# 2021-01-21_HALO_Main_Board-Autorouted.net
KiCad netlist of a schematic drawn in EAGLE
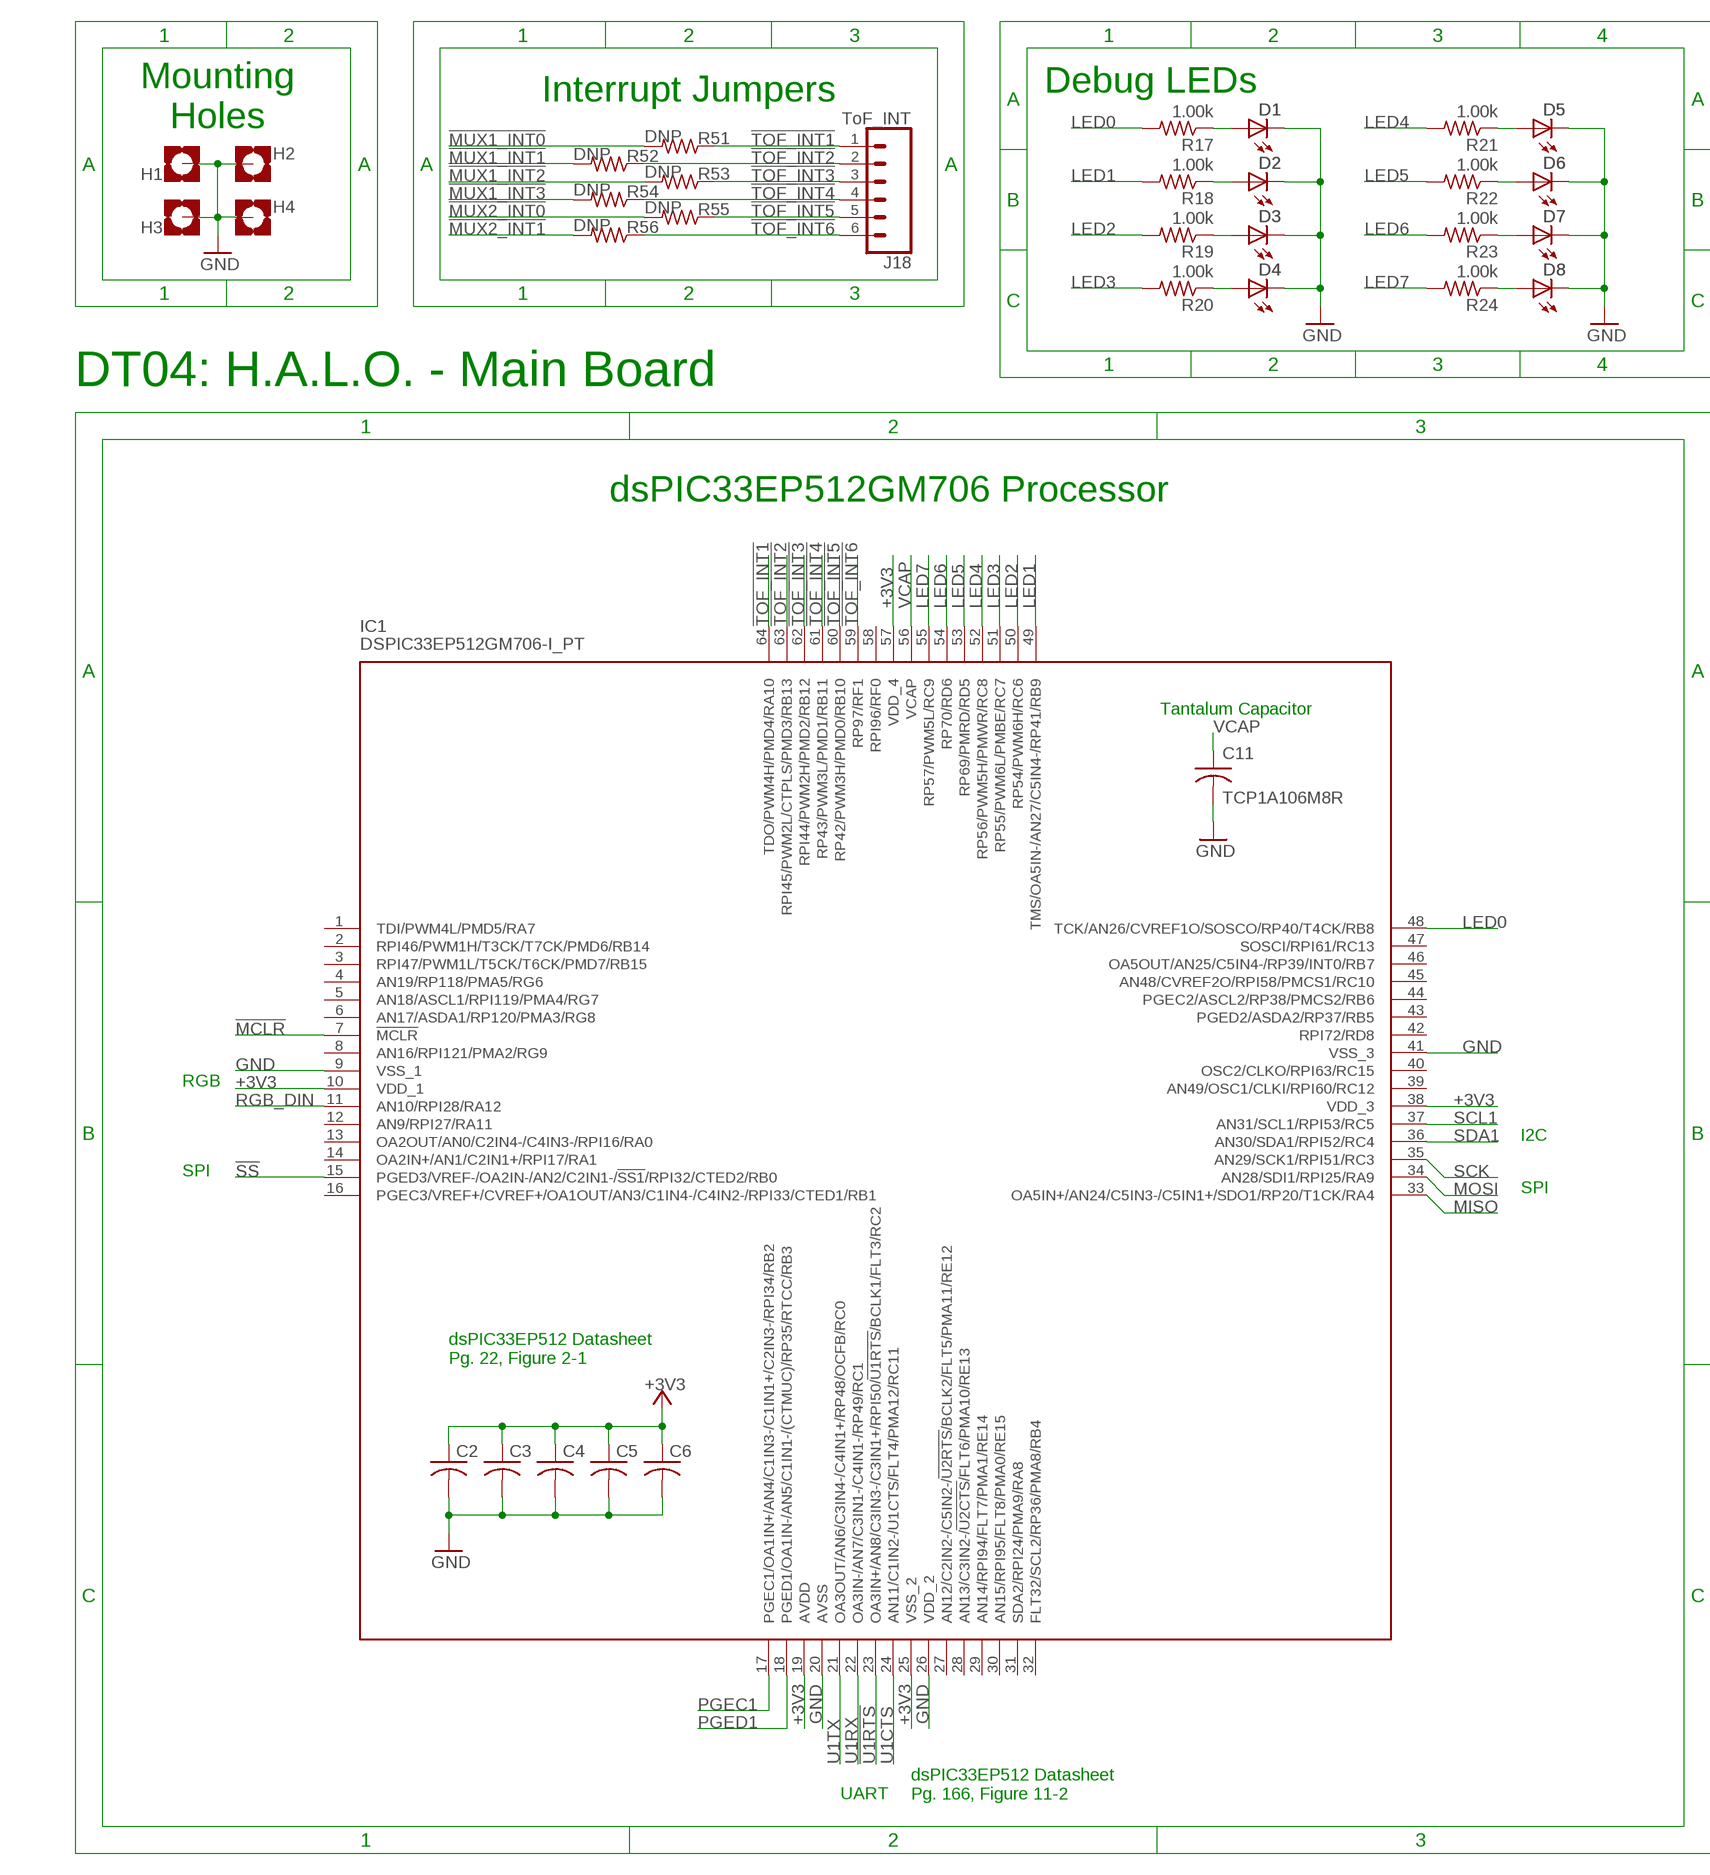
[diagram p0: schematic, sheet 1, part 1 of 2]
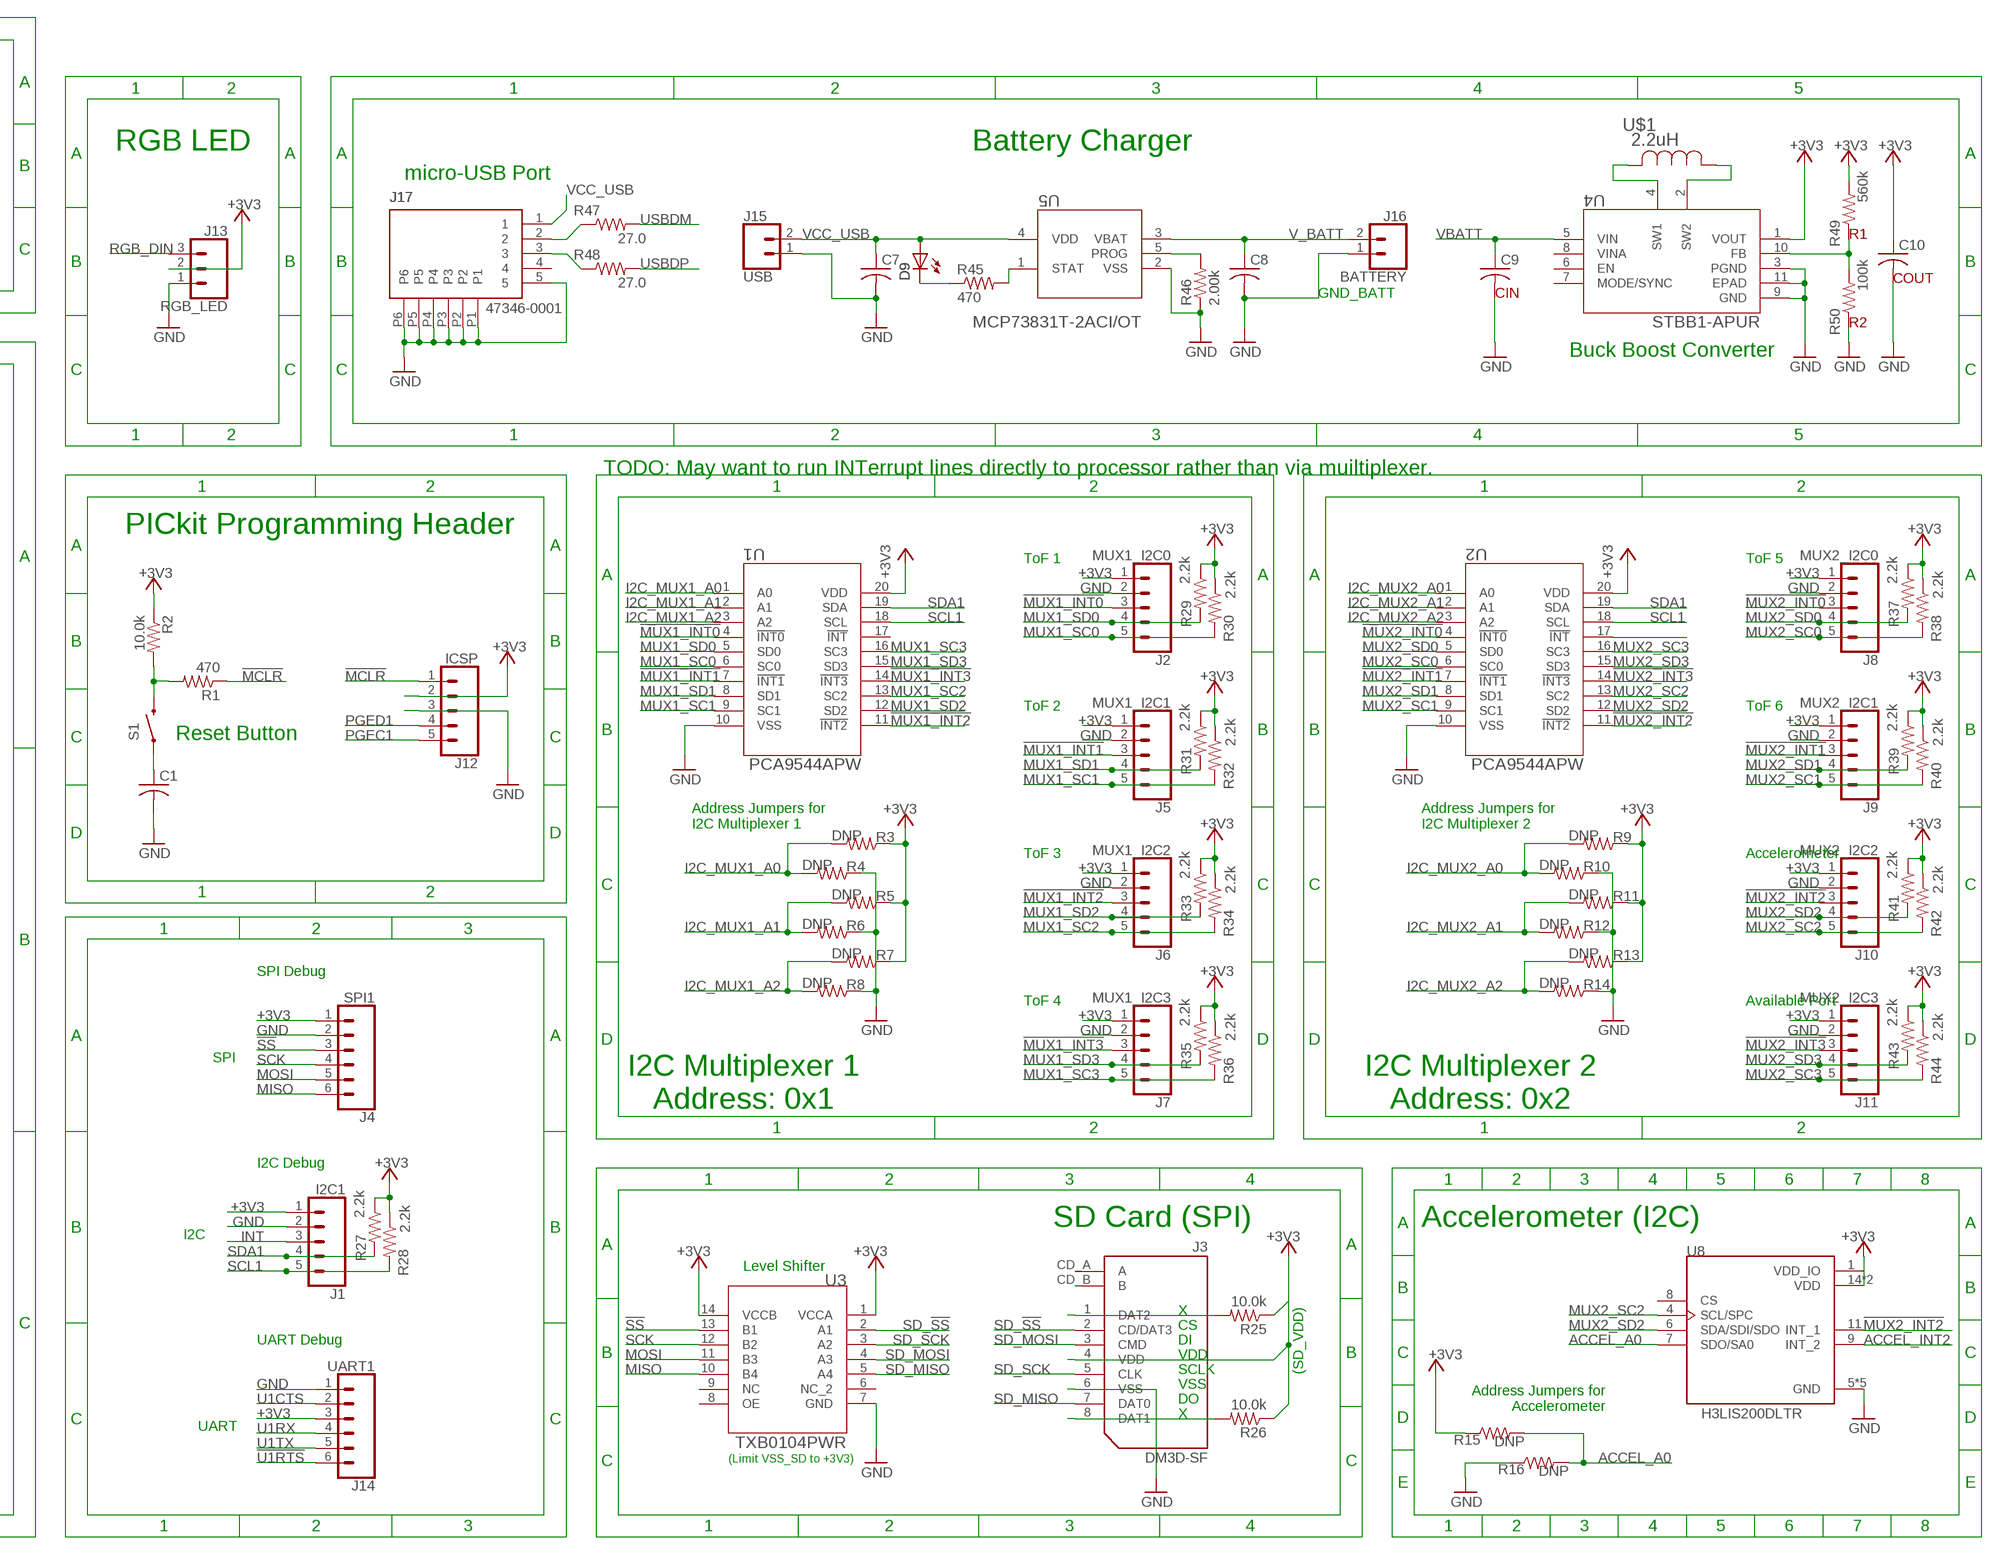
[diagram p1: schematic, sheet 1, part 2 of 2]

(export (version "E")
  (design (tool "Eeschema 10.0.6"))
  (components
    (comp (ref "C1")
      (value "0.1uF")
      (footprint "eagle-import:C0805")
      (libsource (lib "eagle-import") (part "C-USC0805"))
    )
    (comp (ref "C2")
      (value "0.1uF")
      (footprint "eagle-import:C0805")
      (libsource (lib "eagle-import") (part "C-USC0805"))
    )
    (comp (ref "C3")
      (value "0.1uF")
      (footprint "eagle-import:C0805")
      (libsource (lib "eagle-import") (part "C-USC0805"))
    )
    (comp (ref "C4")
      (value "0.1uF")
      (footprint "eagle-import:C0805")
      (libsource (lib "eagle-import") (part "C-USC0805"))
    )
    (comp (ref "C5")
      (value "0.1uF")
      (footprint "eagle-import:C0805")
      (libsource (lib "eagle-import") (part "C-USC0805"))
    )
    (comp (ref "C6")
      (value "0.1uF")
      (footprint "eagle-import:C0805")
      (libsource (lib "eagle-import") (part "C-USC0805"))
    )
    (comp (ref "C7")
      (value "4.7uF")
      (footprint "eagle-import:C0805")
      (libsource (lib "eagle-import") (part "C-USC0805"))
    )
    (comp (ref "C8")
      (value "4.7uF")
      (footprint "eagle-import:C0805")
      (libsource (lib "eagle-import") (part "C-USC0805"))
    )
    (comp (ref "C9")
      (value "10uF")
      (footprint "eagle-import:C0805")
      (libsource (lib "eagle-import") (part "C-USC0805"))
    )
    (comp (ref "C10")
      (value "22uF")
      (footprint "eagle-import:C0805")
      (libsource (lib "eagle-import") (part "C-USC0805"))
    )
    (comp (ref "C11")
      (value "TCP1A106M8R")
      (footprint "eagle-import:TCP_ROM")
      (libsource (lib "eagle-import") (part "TCP1A106M8R"))
    )
    (comp (ref "D1")
      (value "CHIP-LED0805")
      (footprint "eagle-import:CHIP-LED0805")
      (libsource (lib "eagle-import") (part "CHIP-LED0805"))
    )
    (comp (ref "D2")
      (value "CHIP-LED0805")
      (footprint "eagle-import:CHIP-LED0805")
      (libsource (lib "eagle-import") (part "CHIP-LED0805"))
    )
    (comp (ref "D3")
      (value "CHIP-LED0805")
      (footprint "eagle-import:CHIP-LED0805")
      (libsource (lib "eagle-import") (part "CHIP-LED0805"))
    )
    (comp (ref "D4")
      (value "CHIP-LED0805")
      (footprint "eagle-import:CHIP-LED0805")
      (libsource (lib "eagle-import") (part "CHIP-LED0805"))
    )
    (comp (ref "D5")
      (value "CHIP-LED0805")
      (footprint "eagle-import:CHIP-LED0805")
      (libsource (lib "eagle-import") (part "CHIP-LED0805"))
    )
    (comp (ref "D6")
      (value "CHIP-LED0805")
      (footprint "eagle-import:CHIP-LED0805")
      (libsource (lib "eagle-import") (part "CHIP-LED0805"))
    )
    (comp (ref "D7")
      (value "CHIP-LED0805")
      (footprint "eagle-import:CHIP-LED0805")
      (libsource (lib "eagle-import") (part "CHIP-LED0805"))
    )
    (comp (ref "D8")
      (value "CHIP-LED0805")
      (footprint "eagle-import:CHIP-LED0805")
      (libsource (lib "eagle-import") (part "CHIP-LED0805"))
    )
    (comp (ref "D9")
      (value "CHIP-LED0805")
      (footprint "eagle-import:CHIP-LED0805")
      (libsource (lib "eagle-import") (part "CHIP-LED0805"))
    )
    (comp (ref "H1")
      (value "MOUNT-PAD-SQUARE3.0")
      (footprint "eagle-import:3,0-PAD-SQUARE")
      (libsource (lib "eagle-import") (part "MOUNT-PAD-SQUARE3.0"))
    )
    (comp (ref "H2")
      (value "MOUNT-PAD-SQUARE3.0")
      (footprint "eagle-import:3,0-PAD-SQUARE")
      (libsource (lib "eagle-import") (part "MOUNT-PAD-SQUARE3.0"))
    )
    (comp (ref "H3")
      (value "MOUNT-PAD-SQUARE3.0")
      (footprint "eagle-import:3,0-PAD-SQUARE")
      (libsource (lib "eagle-import") (part "MOUNT-PAD-SQUARE3.0"))
    )
    (comp (ref "H4")
      (value "MOUNT-PAD-SQUARE3.0")
      (footprint "eagle-import:3,0-PAD-SQUARE")
      (libsource (lib "eagle-import") (part "MOUNT-PAD-SQUARE3.0"))
    )
    (comp (ref "IC1")
      (value "DSPIC33EP512GM706-I_PT")
      (footprint "eagle-import:QFP50P1200X1200X120-64N")
      (fields
        (field (name "ARROW_PART_NUMBER") "DSPIC33EP512GM706-I/PT")
        (field (name "MOUSER_PART_NUMBER") "579-512GM706-I/PT")
      )
      (libsource (lib "eagle-import") (part "DSPIC33EP512GM706-I_PT"))
    )
    (comp (ref "J1")
      (value "I2C1")
      (footprint "eagle-import:1X05")
      (libsource (lib "eagle-import") (part "CONN_05"))
    )
    (comp (ref "J2")
      (value "MUX1_I2C0")
      (footprint "eagle-import:1X05")
      (libsource (lib "eagle-import") (part "CONN_05"))
    )
    (comp (ref "J3")
      (value "DM3D-SF")
      (footprint "eagle-import:SD_CARD")
      (fields (field (name "PARTNO") "AS-ITM-00047"))
      (libsource (lib "eagle-import") (part "AS-ITM-00047"))
    )
    (comp (ref "J4")
      (value "SPI1")
      (footprint "eagle-import:1X06")
      (libsource (lib "eagle-import") (part "CONN_06SILK_FEMALE_PTH"))
    )
    (comp (ref "J5")
      (value "MUX1_I2C1")
      (footprint "eagle-import:1X05")
      (libsource (lib "eagle-import") (part "CONN_05"))
    )
    (comp (ref "J6")
      (value "MUX1_I2C2")
      (footprint "eagle-import:1X05")
      (libsource (lib "eagle-import") (part "CONN_05"))
    )
    (comp (ref "J7")
      (value "MUX1_I2C3")
      (footprint "eagle-import:1X05")
      (libsource (lib "eagle-import") (part "CONN_05"))
    )
    (comp (ref "J8")
      (value "MUX2_I2C0")
      (footprint "eagle-import:1X05")
      (libsource (lib "eagle-import") (part "CONN_05"))
    )
    (comp (ref "J9")
      (value "MUX2_I2C1")
      (footprint "eagle-import:1X05")
      (libsource (lib "eagle-import") (part "CONN_05"))
    )
    (comp (ref "J10")
      (value "MUX2_I2C2")
      (footprint "eagle-import:1X05")
      (libsource (lib "eagle-import") (part "CONN_05"))
    )
    (comp (ref "J11")
      (value "MUX2_I2C3")
      (footprint "eagle-import:1X05")
      (libsource (lib "eagle-import") (part "CONN_05"))
    )
    (comp (ref "J12")
      (value "ICSP")
      (footprint "eagle-import:1X05")
      (libsource (lib "eagle-import") (part "CONN_05"))
    )
    (comp (ref "J13")
      (value "RGB_LED")
      (footprint "eagle-import:1X03_LOCK")
      (libsource (lib "eagle-import") (part "CONN_03LOCK"))
    )
    (comp (ref "J14")
      (value "UART1")
      (footprint "eagle-import:1X06")
      (libsource (lib "eagle-import") (part "CONN_06SILK_FEMALE_PTH"))
    )
    (comp (ref "J15")
      (value "USB")
      (footprint "eagle-import:1X02")
      (libsource (lib "eagle-import") (part "CONN_02"))
    )
    (comp (ref "J16")
      (value "BATTERY")
      (footprint "eagle-import:1X02")
      (libsource (lib "eagle-import") (part "CONN_02"))
    )
    (comp (ref "J17")
      (value "47346-0001")
      (footprint "eagle-import:MICRO_USB")
      (fields (field (name "PARTNO") "AS-ITM-00021") (field (name "PARTNO_1") "AS-ITM-00021"))
      (libsource (lib "eagle-import") (part "AS-ITM-00021"))
    )
    (comp (ref "J18")
      (value "ToF_INT")
      (footprint "eagle-import:1X06")
      (libsource (lib "eagle-import") (part "CONN_06SILK_FEMALE_PTH"))
    )
    (comp (ref "R1")
      (value "470")
      (footprint "eagle-import:R0805")
      (libsource (lib "eagle-import") (part "R-US_R0805"))
    )
    (comp (ref "R2")
      (value "10.0k")
      (footprint "eagle-import:R0805")
      (libsource (lib "eagle-import") (part "R-US_R0805"))
    )
    (comp (ref "R3")
      (value "DNP")
      (footprint "eagle-import:R0805")
      (libsource (lib "eagle-import") (part "R-US_R0805"))
    )
    (comp (ref "R4")
      (value "DNP")
      (footprint "eagle-import:R0805")
      (libsource (lib "eagle-import") (part "R-US_R0805"))
    )
    (comp (ref "R5")
      (value "DNP")
      (footprint "eagle-import:R0805")
      (libsource (lib "eagle-import") (part "R-US_R0805"))
    )
    (comp (ref "R6")
      (value "DNP")
      (footprint "eagle-import:R0805")
      (libsource (lib "eagle-import") (part "R-US_R0805"))
    )
    (comp (ref "R7")
      (value "DNP")
      (footprint "eagle-import:R0805")
      (libsource (lib "eagle-import") (part "R-US_R0805"))
    )
    (comp (ref "R8")
      (value "DNP")
      (footprint "eagle-import:R0805")
      (libsource (lib "eagle-import") (part "R-US_R0805"))
    )
    (comp (ref "R9")
      (value "DNP")
      (footprint "eagle-import:R0805")
      (libsource (lib "eagle-import") (part "R-US_R0805"))
    )
    (comp (ref "R10")
      (value "DNP")
      (footprint "eagle-import:R0805")
      (libsource (lib "eagle-import") (part "R-US_R0805"))
    )
    (comp (ref "R11")
      (value "DNP")
      (footprint "eagle-import:R0805")
      (libsource (lib "eagle-import") (part "R-US_R0805"))
    )
    (comp (ref "R12")
      (value "DNP")
      (footprint "eagle-import:R0805")
      (libsource (lib "eagle-import") (part "R-US_R0805"))
    )
    (comp (ref "R13")
      (value "DNP")
      (footprint "eagle-import:R0805")
      (libsource (lib "eagle-import") (part "R-US_R0805"))
    )
    (comp (ref "R14")
      (value "DNP")
      (footprint "eagle-import:R0805")
      (libsource (lib "eagle-import") (part "R-US_R0805"))
    )
    (comp (ref "R15")
      (value "DNP")
      (footprint "eagle-import:R0805")
      (libsource (lib "eagle-import") (part "R-US_R0805"))
    )
    (comp (ref "R16")
      (value "DNP")
      (footprint "eagle-import:R0805")
      (libsource (lib "eagle-import") (part "R-US_R0805"))
    )
    (comp (ref "R17")
      (value "1.00k")
      (footprint "eagle-import:R0805")
      (libsource (lib "eagle-import") (part "R-US_R0805"))
    )
    (comp (ref "R18")
      (value "1.00k")
      (footprint "eagle-import:R0805")
      (libsource (lib "eagle-import") (part "R-US_R0805"))
    )
    (comp (ref "R19")
      (value "1.00k")
      (footprint "eagle-import:R0805")
      (libsource (lib "eagle-import") (part "R-US_R0805"))
    )
    (comp (ref "R20")
      (value "1.00k")
      (footprint "eagle-import:R0805")
      (libsource (lib "eagle-import") (part "R-US_R0805"))
    )
    (comp (ref "R21")
      (value "1.00k")
      (footprint "eagle-import:R0805")
      (libsource (lib "eagle-import") (part "R-US_R0805"))
    )
    (comp (ref "R22")
      (value "1.00k")
      (footprint "eagle-import:R0805")
      (libsource (lib "eagle-import") (part "R-US_R0805"))
    )
    (comp (ref "R23")
      (value "1.00k")
      (footprint "eagle-import:R0805")
      (libsource (lib "eagle-import") (part "R-US_R0805"))
    )
    (comp (ref "R24")
      (value "1.00k")
      (footprint "eagle-import:R0805")
      (libsource (lib "eagle-import") (part "R-US_R0805"))
    )
    (comp (ref "R25")
      (value "10.0k")
      (footprint "eagle-import:R0805")
      (libsource (lib "eagle-import") (part "R-US_R0805"))
    )
    (comp (ref "R26")
      (value "10.0k")
      (footprint "eagle-import:R0805")
      (libsource (lib "eagle-import") (part "R-US_R0805"))
    )
    (comp (ref "R27")
      (value "2.2k")
      (footprint "eagle-import:R0805")
      (libsource (lib "eagle-import") (part "R-US_R0805"))
    )
    (comp (ref "R28")
      (value "2.2k")
      (footprint "eagle-import:R0805")
      (libsource (lib "eagle-import") (part "R-US_R0805"))
    )
    (comp (ref "R29")
      (value "2.2k")
      (footprint "eagle-import:R0805")
      (libsource (lib "eagle-import") (part "R-US_R0805"))
    )
    (comp (ref "R30")
      (value "2.2k")
      (footprint "eagle-import:R0805")
      (libsource (lib "eagle-import") (part "R-US_R0805"))
    )
    (comp (ref "R31")
      (value "2.2k")
      (footprint "eagle-import:R0805")
      (libsource (lib "eagle-import") (part "R-US_R0805"))
    )
    (comp (ref "R32")
      (value "2.2k")
      (footprint "eagle-import:R0805")
      (libsource (lib "eagle-import") (part "R-US_R0805"))
    )
    (comp (ref "R33")
      (value "2.2k")
      (footprint "eagle-import:R0805")
      (libsource (lib "eagle-import") (part "R-US_R0805"))
    )
    (comp (ref "R34")
      (value "2.2k")
      (footprint "eagle-import:R0805")
      (libsource (lib "eagle-import") (part "R-US_R0805"))
    )
    (comp (ref "R35")
      (value "2.2k")
      (footprint "eagle-import:R0805")
      (libsource (lib "eagle-import") (part "R-US_R0805"))
    )
    (comp (ref "R36")
      (value "2.2k")
      (footprint "eagle-import:R0805")
      (libsource (lib "eagle-import") (part "R-US_R0805"))
    )
    (comp (ref "R37")
      (value "2.2k")
      (footprint "eagle-import:R0805")
      (libsource (lib "eagle-import") (part "R-US_R0805"))
    )
    (comp (ref "R38")
      (value "2.2k")
      (footprint "eagle-import:R0805")
      (libsource (lib "eagle-import") (part "R-US_R0805"))
    )
    (comp (ref "R39")
      (value "2.2k")
      (footprint "eagle-import:R0805")
      (libsource (lib "eagle-import") (part "R-US_R0805"))
    )
    (comp (ref "R40")
      (value "2.2k")
      (footprint "eagle-import:R0805")
      (libsource (lib "eagle-import") (part "R-US_R0805"))
    )
    (comp (ref "R41")
      (value "2.2k")
      (footprint "eagle-import:R0805")
      (libsource (lib "eagle-import") (part "R-US_R0805"))
    )
    (comp (ref "R42")
      (value "2.2k")
      (footprint "eagle-import:R0805")
      (libsource (lib "eagle-import") (part "R-US_R0805"))
    )
    (comp (ref "R43")
      (value "2.2k")
      (footprint "eagle-import:R0805")
      (libsource (lib "eagle-import") (part "R-US_R0805"))
    )
    (comp (ref "R44")
      (value "2.2k")
      (footprint "eagle-import:R0805")
      (libsource (lib "eagle-import") (part "R-US_R0805"))
    )
    (comp (ref "R45")
      (value "470")
      (footprint "eagle-import:R0805")
      (libsource (lib "eagle-import") (part "R-US_R0805"))
    )
    (comp (ref "R46")
      (value "2.00k")
      (footprint "eagle-import:R0805")
      (libsource (lib "eagle-import") (part "R-US_R0805"))
    )
    (comp (ref "R47")
      (value "27.0")
      (footprint "eagle-import:R0805")
      (libsource (lib "eagle-import") (part "R-US_R0805"))
    )
    (comp (ref "R48")
      (value "27.0")
      (footprint "eagle-import:R0805")
      (libsource (lib "eagle-import") (part "R-US_R0805"))
    )
    (comp (ref "R49")
      (value "560k")
      (footprint "eagle-import:R0805")
      (libsource (lib "eagle-import") (part "R-US_R0805"))
    )
    (comp (ref "R50")
      (value "100k")
      (footprint "eagle-import:R0805")
      (libsource (lib "eagle-import") (part "R-US_R0805"))
    )
    (comp (ref "R51")
      (value "DNP")
      (footprint "eagle-import:R0805")
      (libsource (lib "eagle-import") (part "R-US_R0805"))
    )
    (comp (ref "R52")
      (value "DNP")
      (footprint "eagle-import:R0805")
      (libsource (lib "eagle-import") (part "R-US_R0805"))
    )
    (comp (ref "R53")
      (value "DNP")
      (footprint "eagle-import:R0805")
      (libsource (lib "eagle-import") (part "R-US_R0805"))
    )
    (comp (ref "R54")
      (value "DNP")
      (footprint "eagle-import:R0805")
      (libsource (lib "eagle-import") (part "R-US_R0805"))
    )
    (comp (ref "R55")
      (value "DNP")
      (footprint "eagle-import:R0805")
      (libsource (lib "eagle-import") (part "R-US_R0805"))
    )
    (comp (ref "R56")
      (value "DNP")
      (footprint "eagle-import:R0805")
      (libsource (lib "eagle-import") (part "R-US_R0805"))
    )
    (comp (ref "S1")
      (value "SWITCH-MOMENTARY-2SMD-4")
      (footprint "eagle-import:TACTILE_SWITCH_TALL")
      (libsource (lib "eagle-import") (part "SWITCH-MOMENTARY-2SMD-4"))
    )
    (comp (ref "U$1")
      (value "2.2uH")
      (footprint "eagle-import:IND_4028_TDK")
      (libsource (lib "eagle-import") (part "IND"))
    )
    (comp (ref "U1")
      (value "PCA9544APW")
      (footprint "eagle-import:SOT360-1_NXP")
      (libsource (lib "eagle-import") (part "PCA9544APW"))
    )
    (comp (ref "U2")
      (value "PCA9544APW")
      (footprint "eagle-import:SOT360-1_NXP")
      (libsource (lib "eagle-import") (part "PCA9544APW"))
    )
    (comp (ref "U3")
      (value "TXB0104PWR")
      (footprint "eagle-import:PW14")
      (fields
        (field (name "GENERIC_PART_NUMBER") "TXB0104")
        (field (name "MANUFACTURER") "Texas Instruments")
      )
      (libsource (lib "eagle-import") (part "TXB0104PWR"))
    )
    (comp (ref "U4")
      (value "STBB1-APUR")
      (footprint "eagle-import:SON_B1-APUR_STM")
      (libsource (lib "eagle-import") (part "STBB1-APUR"))
    )
    (comp (ref "U5")
      (value "MCP73831T-2ACI/OT")
      (footprint "eagle-import:SOT-23-5_MC_MCH")
      (libsource (lib "eagle-import") (part "MCP73831T-2ACI/OT"))
    )
    (comp (ref "U8")
      (value "H3LIS200DLTR")
      (footprint "eagle-import:PQFN50P300X300X100-16N")
      (fields (field (name "DIGI-KEY_PART_NUMBER") "497-15698-1-ND") (field (name "MF") "STMicroelectronics"))
      (libsource (lib "eagle-import") (part "H3LIS200DLTR"))
    )
  )
  (nets
    (net (code "1") (name "+3V3") (class "Default")
      (node (ref "C10") (pin "1") (pinfunction "1_1") (pintype "passive"))
      (node (ref "C2") (pin "1") (pinfunction "1_1") (pintype "passive"))
      (node (ref "C3") (pin "1") (pinfunction "1_1") (pintype "passive"))
      (node (ref "C4") (pin "1") (pinfunction "1_1") (pintype "passive"))
      (node (ref "C5") (pin "1") (pinfunction "1_1") (pintype "passive"))
      (node (ref "C6") (pin "1") (pinfunction "1_1") (pintype "passive"))
      (node (ref "IC1") (pin "10") (pinfunction "VDD_1_10") (pintype "bidirectional"))
      (node (ref "IC1") (pin "19") (pinfunction "AVDD_19") (pintype "bidirectional"))
      (node (ref "IC1") (pin "25") (pinfunction "VSS_2_25") (pintype "bidirectional"))
      (node (ref "IC1") (pin "38") (pinfunction "VDD_3_38") (pintype "bidirectional"))
      (node (ref "IC1") (pin "57") (pinfunction "VDD_4_57") (pintype "bidirectional"))
      (node (ref "J1") (pin "1") (pinfunction "1_1") (pintype "passive"))
      (node (ref "J10") (pin "1") (pinfunction "1_1") (pintype "passive"))
      (node (ref "J11") (pin "1") (pinfunction "1_1") (pintype "passive"))
      (node (ref "J12") (pin "2") (pinfunction "2_2") (pintype "passive"))
      (node (ref "J13") (pin "2") (pinfunction "2_2") (pintype "passive"))
      (node (ref "J14") (pin "3") (pinfunction "3_3") (pintype "passive"))
      (node (ref "J2") (pin "1") (pinfunction "1_1") (pintype "passive"))
      (node (ref "J3") (pin "4") (pinfunction "VDD_4") (pintype "bidirectional"))
      (node (ref "J4") (pin "1") (pinfunction "1_1") (pintype "passive"))
      (node (ref "J5") (pin "1") (pinfunction "1_1") (pintype "passive"))
      (node (ref "J6") (pin "1") (pinfunction "1_1") (pintype "passive"))
      (node (ref "J7") (pin "1") (pinfunction "1_1") (pintype "passive"))
      (node (ref "J8") (pin "1") (pinfunction "1_1") (pintype "passive"))
      (node (ref "J9") (pin "1") (pinfunction "1_1") (pintype "passive"))
      (node (ref "R11") (pin "1") (pinfunction "1_1") (pintype "passive"))
      (node (ref "R13") (pin "1") (pinfunction "1_1") (pintype "passive"))
      (node (ref "R15") (pin "1") (pinfunction "1_1") (pintype "passive"))
      (node (ref "R2") (pin "1") (pinfunction "1_1") (pintype "passive"))
      (node (ref "R25") (pin "1") (pinfunction "1_1") (pintype "passive"))
      (node (ref "R26") (pin "1") (pinfunction "1_1") (pintype "passive"))
      (node (ref "R27") (pin "1") (pinfunction "1_1") (pintype "passive"))
      (node (ref "R28") (pin "1") (pinfunction "1_1") (pintype "passive"))
      (node (ref "R29") (pin "1") (pinfunction "1_1") (pintype "passive"))
      (node (ref "R3") (pin "1") (pinfunction "1_1") (pintype "passive"))
      (node (ref "R30") (pin "1") (pinfunction "1_1") (pintype "passive"))
      (node (ref "R31") (pin "1") (pinfunction "1_1") (pintype "passive"))
      (node (ref "R32") (pin "1") (pinfunction "1_1") (pintype "passive"))
      (node (ref "R33") (pin "1") (pinfunction "1_1") (pintype "passive"))
      (node (ref "R34") (pin "1") (pinfunction "1_1") (pintype "passive"))
      (node (ref "R35") (pin "1") (pinfunction "1_1") (pintype "passive"))
      (node (ref "R36") (pin "1") (pinfunction "1_1") (pintype "passive"))
      (node (ref "R37") (pin "1") (pinfunction "1_1") (pintype "passive"))
      (node (ref "R38") (pin "1") (pinfunction "1_1") (pintype "passive"))
      (node (ref "R39") (pin "1") (pinfunction "1_1") (pintype "passive"))
      (node (ref "R40") (pin "1") (pinfunction "1_1") (pintype "passive"))
      (node (ref "R41") (pin "1") (pinfunction "1_1") (pintype "passive"))
      (node (ref "R42") (pin "1") (pinfunction "1_1") (pintype "passive"))
      (node (ref "R43") (pin "1") (pinfunction "1_1") (pintype "passive"))
      (node (ref "R44") (pin "1") (pinfunction "1_1") (pintype "passive"))
      (node (ref "R49") (pin "2") (pinfunction "2_2") (pintype "passive"))
      (node (ref "R5") (pin "1") (pinfunction "1_1") (pintype "passive"))
      (node (ref "R7") (pin "1") (pinfunction "1_1") (pintype "passive"))
      (node (ref "R9") (pin "1") (pinfunction "1_1") (pintype "passive"))
      (node (ref "U1") (pin "20") (pinfunction "VDD_20") (pintype "passive"))
      (node (ref "U2") (pin "20") (pinfunction "VDD_20") (pintype "passive"))
      (node (ref "U3") (pin "1") (pinfunction "VCCA_1") (pintype "power_in"))
      (node (ref "U3") (pin "14") (pinfunction "VCCB_14") (pintype "power_in"))
      (node (ref "U4") (pin "1") (pinfunction "VOUT_1") (pintype "power_in"))
      (node (ref "U8") (pin "1") (pinfunction "VDD_IO_1") (pintype "power_in"))
      (node (ref "U8") (pin "14") (pinfunction "VDD_14") (pintype "power_in"))
      (node (ref "U8") (pin "15") (pinfunction "VDD_15") (pintype "power_in"))
    )
    (net (code "2") (name "/ACCEL_A0") (class "Default")
      (node (ref "R15") (pin "2") (pinfunction "2_2") (pintype "passive"))
      (node (ref "R16") (pin "2") (pinfunction "2_2") (pintype "passive"))
      (node (ref "U8") (pin "7") (pinfunction "SDO/SA0_7") (pintype "output"))
    )
    (net (code "3") (name "/ACCEL_INT2") (class "Default")
      (node (ref "U8") (pin "9") (pinfunction "INT_2_9") (pintype "output"))
    )
    (net (code "4") (name "/I2C_MUX1_A0") (class "Default")
      (node (ref "R3") (pin "2") (pinfunction "2_2") (pintype "passive"))
      (node (ref "R4") (pin "2") (pinfunction "2_2") (pintype "passive"))
      (node (ref "U1") (pin "1") (pinfunction "A0_1") (pintype "passive"))
    )
    (net (code "5") (name "/I2C_MUX1_A1") (class "Default")
      (node (ref "R5") (pin "2") (pinfunction "2_2") (pintype "passive"))
      (node (ref "R6") (pin "2") (pinfunction "2_2") (pintype "passive"))
      (node (ref "U1") (pin "2") (pinfunction "A1_2") (pintype "passive"))
    )
    (net (code "6") (name "/I2C_MUX1_A2") (class "Default")
      (node (ref "R7") (pin "2") (pinfunction "2_2") (pintype "passive"))
      (node (ref "R8") (pin "2") (pinfunction "2_2") (pintype "passive"))
      (node (ref "U1") (pin "3") (pinfunction "A2_3") (pintype "passive"))
    )
    (net (code "7") (name "/I2C_MUX2_A0") (class "Default")
      (node (ref "R10") (pin "2") (pinfunction "2_2") (pintype "passive"))
      (node (ref "R9") (pin "2") (pinfunction "2_2") (pintype "passive"))
      (node (ref "U2") (pin "1") (pinfunction "A0_1") (pintype "passive"))
    )
    (net (code "8") (name "/I2C_MUX2_A1") (class "Default")
      (node (ref "R11") (pin "2") (pinfunction "2_2") (pintype "passive"))
      (node (ref "R12") (pin "2") (pinfunction "2_2") (pintype "passive"))
      (node (ref "U2") (pin "2") (pinfunction "A1_2") (pintype "passive"))
    )
    (net (code "9") (name "/I2C_MUX2_A2") (class "Default")
      (node (ref "R13") (pin "2") (pinfunction "2_2") (pintype "passive"))
      (node (ref "R14") (pin "2") (pinfunction "2_2") (pintype "passive"))
      (node (ref "U2") (pin "3") (pinfunction "A2_3") (pintype "passive"))
    )
    (net (code "10") (name "/INT") (class "Default")
      (node (ref "J1") (pin "3") (pinfunction "3_3") (pintype "passive"))
    )
    (net (code "11") (name "/LED0") (class "Default")
      (node (ref "IC1") (pin "48") (pinfunction "TCK/AN26/CVREF1O/SOSCO/RP40/T4CK/RB8_48") (pintype "bidirectional"))
      (node (ref "R17") (pin "2") (pinfunction "2_2") (pintype "passive"))
    )
    (net (code "12") (name "/LED1") (class "Default")
      (node (ref "IC1") (pin "49") (pinfunction "TMS/OA5IN-/AN27/C5IN4-/RP41/RB9_49") (pintype "bidirectional"))
      (node (ref "R18") (pin "2") (pinfunction "2_2") (pintype "passive"))
    )
    (net (code "13") (name "/LED2") (class "Default")
      (node (ref "IC1") (pin "50") (pinfunction "RP54/PWM6H/RC6_50") (pintype "bidirectional"))
      (node (ref "R19") (pin "2") (pinfunction "2_2") (pintype "passive"))
    )
    (net (code "14") (name "/LED3") (class "Default")
      (node (ref "IC1") (pin "51") (pinfunction "RP55/PWM6L/PMBE/RC7_51") (pintype "bidirectional"))
      (node (ref "R20") (pin "2") (pinfunction "2_2") (pintype "passive"))
    )
    (net (code "15") (name "/LED4") (class "Default")
      (node (ref "IC1") (pin "52") (pinfunction "RP56/PWM5H/PMWR/RC8_52") (pintype "bidirectional"))
      (node (ref "R21") (pin "2") (pinfunction "2_2") (pintype "passive"))
    )
    (net (code "16") (name "/LED5") (class "Default")
      (node (ref "IC1") (pin "53") (pinfunction "RP69/PMRD/RD5_53") (pintype "bidirectional"))
      (node (ref "R22") (pin "2") (pinfunction "2_2") (pintype "passive"))
    )
    (net (code "17") (name "/LED6") (class "Default")
      (node (ref "IC1") (pin "54") (pinfunction "RP70/RD6_54") (pintype "bidirectional"))
      (node (ref "R23") (pin "2") (pinfunction "2_2") (pintype "passive"))
    )
    (net (code "18") (name "/LED7") (class "Default")
      (node (ref "IC1") (pin "55") (pinfunction "RP57/PWM5L/RC9_55") (pintype "bidirectional"))
      (node (ref "R24") (pin "2") (pinfunction "2_2") (pintype "passive"))
    )
    (net (code "19") (name "/MISO") (class "Default")
      (node (ref "IC1") (pin "33") (pinfunction "OA5IN+/AN24/C5IN3-/C5IN1+/SDO1/RP20/T1CK/RA4_33") (pintype "bidirectional"))
      (node (ref "J4") (pin "6") (pinfunction "6_6") (pintype "passive"))
      (node (ref "U3") (pin "10") (pinfunction "B4_10") (pintype "bidirectional"))
    )
    (net (code "20") (name "/MOSI") (class "Default")
      (node (ref "IC1") (pin "34") (pinfunction "AN28/SDI1/RPI25/RA9_34") (pintype "bidirectional"))
      (node (ref "J4") (pin "5") (pinfunction "5_5") (pintype "passive"))
      (node (ref "U3") (pin "11") (pinfunction "B3_11") (pintype "bidirectional"))
    )
    (net (code "21") (name "/MUX1_SC0") (class "Default")
      (node (ref "J2") (pin "5") (pinfunction "5_5") (pintype "passive"))
      (node (ref "R30") (pin "2") (pinfunction "2_2") (pintype "passive"))
      (node (ref "U1") (pin "6") (pinfunction "SC0_6") (pintype "passive"))
    )
    (net (code "22") (name "/MUX1_SC1") (class "Default")
      (node (ref "J5") (pin "5") (pinfunction "5_5") (pintype "passive"))
      (node (ref "R32") (pin "2") (pinfunction "2_2") (pintype "passive"))
      (node (ref "U1") (pin "9") (pinfunction "SC1_9") (pintype "passive"))
    )
    (net (code "23") (name "/MUX1_SC2") (class "Default")
      (node (ref "J6") (pin "5") (pinfunction "5_5") (pintype "passive"))
      (node (ref "R34") (pin "2") (pinfunction "2_2") (pintype "passive"))
      (node (ref "U1") (pin "13") (pinfunction "SC2_13") (pintype "passive"))
    )
    (net (code "24") (name "/MUX1_SC3") (class "Default")
      (node (ref "J7") (pin "5") (pinfunction "5_5") (pintype "passive"))
      (node (ref "R36") (pin "2") (pinfunction "2_2") (pintype "passive"))
      (node (ref "U1") (pin "16") (pinfunction "SC3_16") (pintype "passive"))
    )
    (net (code "25") (name "/MUX1_SD0") (class "Default")
      (node (ref "J2") (pin "4") (pinfunction "4_4") (pintype "passive"))
      (node (ref "R29") (pin "2") (pinfunction "2_2") (pintype "passive"))
      (node (ref "U1") (pin "5") (pinfunction "SD0_5") (pintype "passive"))
    )
    (net (code "26") (name "/MUX1_SD1") (class "Default")
      (node (ref "J5") (pin "4") (pinfunction "4_4") (pintype "passive"))
      (node (ref "R31") (pin "2") (pinfunction "2_2") (pintype "passive"))
      (node (ref "U1") (pin "8") (pinfunction "SD1_8") (pintype "passive"))
    )
    (net (code "27") (name "/MUX1_SD2") (class "Default")
      (node (ref "J6") (pin "4") (pinfunction "4_4") (pintype "passive"))
      (node (ref "R33") (pin "2") (pinfunction "2_2") (pintype "passive"))
      (node (ref "U1") (pin "12") (pinfunction "SD2_12") (pintype "passive"))
    )
    (net (code "28") (name "/MUX1_SD3") (class "Default")
      (node (ref "J7") (pin "4") (pinfunction "4_4") (pintype "passive"))
      (node (ref "R35") (pin "2") (pinfunction "2_2") (pintype "passive"))
      (node (ref "U1") (pin "15") (pinfunction "SD3_15") (pintype "passive"))
    )
    (net (code "29") (name "/MUX2_SC0") (class "Default")
      (node (ref "J8") (pin "5") (pinfunction "5_5") (pintype "passive"))
      (node (ref "R38") (pin "2") (pinfunction "2_2") (pintype "passive"))
      (node (ref "U2") (pin "6") (pinfunction "SC0_6") (pintype "passive"))
    )
    (net (code "30") (name "/MUX2_SC1") (class "Default")
      (node (ref "J9") (pin "5") (pinfunction "5_5") (pintype "passive"))
      (node (ref "R40") (pin "2") (pinfunction "2_2") (pintype "passive"))
      (node (ref "U2") (pin "9") (pinfunction "SC1_9") (pintype "passive"))
    )
    (net (code "31") (name "/MUX2_SC2") (class "Default")
      (node (ref "J10") (pin "5") (pinfunction "5_5") (pintype "passive"))
      (node (ref "R42") (pin "2") (pinfunction "2_2") (pintype "passive"))
      (node (ref "U2") (pin "13") (pinfunction "SC2_13") (pintype "passive"))
      (node (ref "U8") (pin "4") (pinfunction "SCL/SPC_4") (pintype "input"))
    )
    (net (code "32") (name "/MUX2_SC3") (class "Default")
      (node (ref "J11") (pin "5") (pinfunction "5_5") (pintype "passive"))
      (node (ref "R44") (pin "2") (pinfunction "2_2") (pintype "passive"))
      (node (ref "U2") (pin "16") (pinfunction "SC3_16") (pintype "passive"))
    )
    (net (code "33") (name "/MUX2_SD0") (class "Default")
      (node (ref "J8") (pin "4") (pinfunction "4_4") (pintype "passive"))
      (node (ref "R37") (pin "2") (pinfunction "2_2") (pintype "passive"))
      (node (ref "U2") (pin "5") (pinfunction "SD0_5") (pintype "passive"))
    )
    (net (code "34") (name "/MUX2_SD1") (class "Default")
      (node (ref "J9") (pin "4") (pinfunction "4_4") (pintype "passive"))
      (node (ref "R39") (pin "2") (pinfunction "2_2") (pintype "passive"))
      (node (ref "U2") (pin "8") (pinfunction "SD1_8") (pintype "passive"))
    )
    (net (code "35") (name "/MUX2_SD2") (class "Default")
      (node (ref "J10") (pin "4") (pinfunction "4_4") (pintype "passive"))
      (node (ref "R41") (pin "2") (pinfunction "2_2") (pintype "passive"))
      (node (ref "U2") (pin "12") (pinfunction "SD2_12") (pintype "passive"))
      (node (ref "U8") (pin "6") (pinfunction "SDA/SDI/SDO_6") (pintype "bidirectional"))
    )
    (net (code "36") (name "/MUX2_SD3") (class "Default")
      (node (ref "J11") (pin "4") (pinfunction "4_4") (pintype "passive"))
      (node (ref "R43") (pin "2") (pinfunction "2_2") (pintype "passive"))
      (node (ref "U2") (pin "15") (pinfunction "SD3_15") (pintype "passive"))
    )
    (net (code "37") (name "/PGEC1") (class "Default")
      (node (ref "IC1") (pin "17") (pinfunction "PGEC1/OA1IN+/AN4/C1IN3-/C1IN1+/C2IN3-/RPI34/RB2_17") (pintype "bidirectional"))
      (node (ref "J12") (pin "5") (pinfunction "5_5") (pintype "passive"))
    )
    (net (code "38") (name "/PGED1") (class "Default")
      (node (ref "IC1") (pin "18") (pinfunction "PGED1/OA1IN-/AN5/C1IN1-/(CTMUC)/RP35/RTCC/RB3_18") (pintype "bidirectional"))
      (node (ref "J12") (pin "4") (pinfunction "4_4") (pintype "passive"))
    )
    (net (code "39") (name "/RGB_DIN") (class "Default")
      (node (ref "IC1") (pin "11") (pinfunction "AN10/RPI28/RA12_11") (pintype "bidirectional"))
      (node (ref "J13") (pin "3") (pinfunction "3_3") (pintype "passive"))
    )
    (net (code "40") (name "/SCK") (class "Default")
      (node (ref "IC1") (pin "35") (pinfunction "AN29/SCK1/RPI51/RC3_35") (pintype "bidirectional"))
      (node (ref "J4") (pin "4") (pinfunction "4_4") (pintype "passive"))
      (node (ref "U3") (pin "12") (pinfunction "B2_12") (pintype "bidirectional"))
    )
    (net (code "41") (name "/SCL1") (class "Default")
      (node (ref "IC1") (pin "37") (pinfunction "AN31/SCL1/RPI53/RC5_37") (pintype "bidirectional"))
      (node (ref "J1") (pin "5") (pinfunction "5_5") (pintype "passive"))
      (node (ref "R28") (pin "2") (pinfunction "2_2") (pintype "passive"))
      (node (ref "U1") (pin "18") (pinfunction "SCL_18") (pintype "passive"))
      (node (ref "U2") (pin "18") (pinfunction "SCL_18") (pintype "passive"))
    )
    (net (code "42") (name "/SDA1") (class "Default")
      (node (ref "IC1") (pin "36") (pinfunction "AN30/SDA1/RPI52/RC4_36") (pintype "bidirectional"))
      (node (ref "J1") (pin "4") (pinfunction "4_4") (pintype "passive"))
      (node (ref "R27") (pin "2") (pinfunction "2_2") (pintype "passive"))
      (node (ref "U1") (pin "19") (pinfunction "SDA_19") (pintype "passive"))
      (node (ref "U2") (pin "19") (pinfunction "SDA_19") (pintype "passive"))
    )
    (net (code "43") (name "/SD_MISO") (class "Default")
      (node (ref "J3") (pin "7") (pinfunction "DAT0_7") (pintype "bidirectional"))
      (node (ref "U3") (pin "5") (pinfunction "A4_5") (pintype "bidirectional"))
    )
    (net (code "44") (name "/SD_MOSI") (class "Default")
      (node (ref "J3") (pin "3") (pinfunction "CMD_3") (pintype "bidirectional"))
      (node (ref "U3") (pin "4") (pinfunction "A3_4") (pintype "bidirectional"))
    )
    (net (code "45") (name "/SD_SCK") (class "Default")
      (node (ref "J3") (pin "5") (pinfunction "CLK_5") (pintype "bidirectional"))
      (node (ref "U3") (pin "3") (pinfunction "A2_3") (pintype "bidirectional"))
    )
    (net (code "46") (name "/SD_~{SS}") (class "Default")
      (node (ref "J3") (pin "2") (pinfunction "CD/DAT3_2") (pintype "bidirectional"))
      (node (ref "U3") (pin "2") (pinfunction "A1_2") (pintype "bidirectional"))
    )
    (net (code "47") (name "/U1CTS") (class "Default")
      (node (ref "IC1") (pin "24") (pinfunction "AN11/C1IN2-/U1CTS/FLT4/PMA12/RC11_24") (pintype "bidirectional"))
      (node (ref "J14") (pin "2") (pinfunction "2_2") (pintype "passive"))
    )
    (net (code "48") (name "/U1RX") (class "Default")
      (node (ref "IC1") (pin "22") (pinfunction "OA3IN-/AN7/C3IN1-/C4IN1-/RP49/RC1_22") (pintype "bidirectional"))
      (node (ref "J14") (pin "4") (pinfunction "4_4") (pintype "passive"))
    )
    (net (code "49") (name "/U1TX") (class "Default")
      (node (ref "IC1") (pin "21") (pinfunction "OA3OUT/AN6/C3IN4-/C4IN1+/RP48/OCFB/RC0_21") (pintype "bidirectional"))
      (node (ref "J14") (pin "5") (pinfunction "5_5") (pintype "passive"))
    )
    (net (code "50") (name "/USBDM") (class "Default")
      (node (ref "R47") (pin "2") (pinfunction "2_2") (pintype "passive"))
    )
    (net (code "51") (name "/USBDP") (class "Default")
      (node (ref "R48") (pin "2") (pinfunction "2_2") (pintype "passive"))
    )
    (net (code "52") (name "/VBATT") (class "Default")
      (node (ref "C9") (pin "1") (pinfunction "1_1") (pintype "passive"))
      (node (ref "U4") (pin "5") (pinfunction "VIN_5") (pintype "power_in"))
    )
    (net (code "53") (name "/VCAP") (class "Default")
      (node (ref "C11") (pin "1") (pinfunction "1_1") (pintype "passive"))
      (node (ref "IC1") (pin "56") (pinfunction "VCAP_56") (pintype "bidirectional"))
    )
    (net (code "54") (name "/VCC_USB") (class "Default")
      (node (ref "C7") (pin "1") (pinfunction "1_1") (pintype "passive"))
      (node (ref "D9") (pin "A") (pinfunction "A_A") (pintype "passive"))
      (node (ref "J15") (pin "2") (pinfunction "2_2") (pintype "passive"))
      (node (ref "J17") (pin "1") (pinfunction "1_1") (pintype "bidirectional"))
      (node (ref "U5") (pin "4") (pinfunction "VDD_4") (pintype "passive"))
    )
    (net (code "55") (name "/VINA") (class "Default")
      (node (ref "U4") (pin "8") (pinfunction "VINA_8") (pintype "power_in"))
    )
    (net (code "56") (name "/V_BATT") (class "Default")
      (node (ref "C8") (pin "1") (pinfunction "1_1") (pintype "passive"))
      (node (ref "J16") (pin "2") (pinfunction "2_2") (pintype "passive"))
      (node (ref "U5") (pin "3") (pinfunction "VBAT_3") (pintype "passive"))
    )
    (net (code "57") (name "/~{MCLR}") (class "Default")
      (node (ref "IC1") (pin "7") (pinfunction "~{MCLR}_7") (pintype "bidirectional"))
      (node (ref "J12") (pin "1") (pinfunction "1_1") (pintype "passive"))
      (node (ref "R1") (pin "1") (pinfunction "1_1") (pintype "passive"))
    )
    (net (code "58") (name "/~{MUX1_INT0}") (class "Default")
      (node (ref "J2") (pin "3") (pinfunction "3_3") (pintype "passive"))
      (node (ref "R51") (pin "2") (pinfunction "2_2") (pintype "passive"))
      (node (ref "U1") (pin "4") (pinfunction "~{INT0}_4") (pintype "passive"))
    )
    (net (code "59") (name "/~{MUX1_INT1}") (class "Default")
      (node (ref "J5") (pin "3") (pinfunction "3_3") (pintype "passive"))
      (node (ref "R52") (pin "2") (pinfunction "2_2") (pintype "passive"))
      (node (ref "U1") (pin "7") (pinfunction "~{INT1}_7") (pintype "passive"))
    )
    (net (code "60") (name "/~{MUX1_INT2}") (class "Default")
      (node (ref "J6") (pin "3") (pinfunction "3_3") (pintype "passive"))
      (node (ref "R53") (pin "2") (pinfunction "2_2") (pintype "passive"))
      (node (ref "U1") (pin "11") (pinfunction "~{INT2}_11") (pintype "passive"))
    )
    (net (code "61") (name "/~{MUX1_INT3}") (class "Default")
      (node (ref "J7") (pin "3") (pinfunction "3_3") (pintype "passive"))
      (node (ref "R54") (pin "2") (pinfunction "2_2") (pintype "passive"))
      (node (ref "U1") (pin "14") (pinfunction "~{INT3}_14") (pintype "passive"))
    )
    (net (code "62") (name "/~{MUX2_INT0}") (class "Default")
      (node (ref "J8") (pin "3") (pinfunction "3_3") (pintype "passive"))
      (node (ref "R55") (pin "2") (pinfunction "2_2") (pintype "passive"))
      (node (ref "U2") (pin "4") (pinfunction "~{INT0}_4") (pintype "passive"))
    )
    (net (code "63") (name "/~{MUX2_INT1}") (class "Default")
      (node (ref "J9") (pin "3") (pinfunction "3_3") (pintype "passive"))
      (node (ref "R56") (pin "2") (pinfunction "2_2") (pintype "passive"))
      (node (ref "U2") (pin "7") (pinfunction "~{INT1}_7") (pintype "passive"))
    )
    (net (code "64") (name "/~{MUX2_INT2}") (class "Default")
      (node (ref "J10") (pin "3") (pinfunction "3_3") (pintype "passive"))
      (node (ref "U2") (pin "11") (pinfunction "~{INT2}_11") (pintype "passive"))
      (node (ref "U8") (pin "11") (pinfunction "INT_1_11") (pintype "output"))
    )
    (net (code "65") (name "/~{MUX2_INT3}") (class "Default")
      (node (ref "J11") (pin "3") (pinfunction "3_3") (pintype "passive"))
      (node (ref "U2") (pin "14") (pinfunction "~{INT3}_14") (pintype "passive"))
    )
    (net (code "66") (name "/~{SS}") (class "Default")
      (node (ref "IC1") (pin "15") (pinfunction "PGED3/VREF-/OA2IN-/AN2/C2IN1-/~{SS1}/RPI32/CTED2/RB0_15") (pintype "bidirectional"))
      (node (ref "J4") (pin "3") (pinfunction "3_3") (pintype "passive"))
      (node (ref "U3") (pin "13") (pinfunction "B1_13") (pintype "bidirectional"))
    )
    (net (code "67") (name "/~{TOF_INT1}") (class "Default")
      (node (ref "IC1") (pin "64") (pinfunction "TDO/PWM4H/PMD4/RA10_64") (pintype "bidirectional"))
      (node (ref "J18") (pin "1") (pinfunction "1_1") (pintype "passive"))
      (node (ref "R51") (pin "1") (pinfunction "1_1") (pintype "passive"))
    )
    (net (code "68") (name "/~{TOF_INT2}") (class "Default")
      (node (ref "IC1") (pin "63") (pinfunction "RPI45/PWM2L/CTPLS/PMD3/RB13_63") (pintype "bidirectional"))
      (node (ref "J18") (pin "2") (pinfunction "2_2") (pintype "passive"))
      (node (ref "R52") (pin "1") (pinfunction "1_1") (pintype "passive"))
    )
    (net (code "69") (name "/~{TOF_INT3}") (class "Default")
      (node (ref "IC1") (pin "62") (pinfunction "RPI44/PWM2H/PMD2/RB12_62") (pintype "bidirectional"))
      (node (ref "J18") (pin "3") (pinfunction "3_3") (pintype "passive"))
      (node (ref "R53") (pin "1") (pinfunction "1_1") (pintype "passive"))
    )
    (net (code "70") (name "/~{TOF_INT4}") (class "Default")
      (node (ref "IC1") (pin "61") (pinfunction "RP43/PWM3L/PMD1/RB11_61") (pintype "bidirectional"))
      (node (ref "J18") (pin "4") (pinfunction "4_4") (pintype "passive"))
      (node (ref "R54") (pin "1") (pinfunction "1_1") (pintype "passive"))
    )
    (net (code "71") (name "/~{TOF_INT5}") (class "Default")
      (node (ref "IC1") (pin "60") (pinfunction "RP42/PWM3H/PMD0/RB10_60") (pintype "bidirectional"))
      (node (ref "J18") (pin "5") (pinfunction "5_5") (pintype "passive"))
      (node (ref "R55") (pin "1") (pinfunction "1_1") (pintype "passive"))
    )
    (net (code "72") (name "/~{TOF_INT6}") (class "Default")
      (node (ref "IC1") (pin "59") (pinfunction "RP97/RF1_59") (pintype "bidirectional"))
      (node (ref "J18") (pin "6") (pinfunction "6_6") (pintype "passive"))
      (node (ref "R56") (pin "1") (pinfunction "1_1") (pintype "passive"))
    )
    (net (code "73") (name "/~{U1RTS}") (class "Default")
      (node (ref "IC1") (pin "23") (pinfunction "OA3IN+/AN8/C3IN3-/C3IN1+/RPI50/~{U1RTS}/BCLK1/FLT3/RC2_23") (pintype "bidirectional"))
      (node (ref "J14") (pin "6") (pinfunction "6_6") (pintype "passive"))
    )
    (net (code "74") (name "GND") (class "Default")
      (node (ref "C1") (pin "2") (pinfunction "2_2") (pintype "passive"))
      (node (ref "C10") (pin "2") (pinfunction "2_2") (pintype "passive"))
      (node (ref "C11") (pin "2") (pinfunction "2_2") (pintype "passive"))
      (node (ref "C2") (pin "2") (pinfunction "2_2") (pintype "passive"))
      (node (ref "C3") (pin "2") (pinfunction "2_2") (pintype "passive"))
      (node (ref "C4") (pin "2") (pinfunction "2_2") (pintype "passive"))
      (node (ref "C5") (pin "2") (pinfunction "2_2") (pintype "passive"))
      (node (ref "C6") (pin "2") (pinfunction "2_2") (pintype "passive"))
      (node (ref "C7") (pin "2") (pinfunction "2_2") (pintype "passive"))
      (node (ref "C8") (pin "2") (pinfunction "2_2") (pintype "passive"))
      (node (ref "C9") (pin "2") (pinfunction "2_2") (pintype "passive"))
      (node (ref "D1") (pin "C") (pinfunction "C_C") (pintype "passive"))
      (node (ref "D2") (pin "C") (pinfunction "C_C") (pintype "passive"))
      (node (ref "D3") (pin "C") (pinfunction "C_C") (pintype "passive"))
      (node (ref "D4") (pin "C") (pinfunction "C_C") (pintype "passive"))
      (node (ref "D5") (pin "C") (pinfunction "C_C") (pintype "passive"))
      (node (ref "D6") (pin "C") (pinfunction "C_C") (pintype "passive"))
      (node (ref "D7") (pin "C") (pinfunction "C_C") (pintype "passive"))
      (node (ref "D8") (pin "C") (pinfunction "C_C") (pintype "passive"))
      (node (ref "H1") (pin "B3,0") (pinfunction "MOUNT_B3,0") (pintype "passive"))
      (node (ref "H2") (pin "B3,0") (pinfunction "MOUNT_B3,0") (pintype "passive"))
      (node (ref "H3") (pin "B3,0") (pinfunction "MOUNT_B3,0") (pintype "passive"))
      (node (ref "H4") (pin "B3,0") (pinfunction "MOUNT_B3,0") (pintype "passive"))
      (node (ref "IC1") (pin "20") (pinfunction "AVSS_20") (pintype "bidirectional"))
      (node (ref "IC1") (pin "26") (pinfunction "VDD_2_26") (pintype "bidirectional"))
      (node (ref "IC1") (pin "41") (pinfunction "VSS_3_41") (pintype "bidirectional"))
      (node (ref "IC1") (pin "9") (pinfunction "VSS_1_9") (pintype "bidirectional"))
      (node (ref "J1") (pin "2") (pinfunction "2_2") (pintype "passive"))
      (node (ref "J10") (pin "2") (pinfunction "2_2") (pintype "passive"))
      (node (ref "J11") (pin "2") (pinfunction "2_2") (pintype "passive"))
      (node (ref "J12") (pin "3") (pinfunction "3_3") (pintype "passive"))
      (node (ref "J13") (pin "1") (pinfunction "1_1") (pintype "passive"))
      (node (ref "J14") (pin "1") (pinfunction "1_1") (pintype "passive"))
      (node (ref "J15") (pin "1") (pinfunction "1_1") (pintype "passive"))
      (node (ref "J16") (pin "1") (pinfunction "1_1") (pintype "passive"))
      (node (ref "J17") (pin "5") (pinfunction "5_5") (pintype "bidirectional"))
      (node (ref "J17") (pin "P1") (pinfunction "P1_P1") (pintype "bidirectional"))
      (node (ref "J17") (pin "P2") (pinfunction "P2_P2") (pintype "bidirectional"))
      (node (ref "J17") (pin "P3") (pinfunction "P3_P3") (pintype "bidirectional"))
      (node (ref "J17") (pin "P4") (pinfunction "P4_P4") (pintype "bidirectional"))
      (node (ref "J17") (pin "P5") (pinfunction "P5_P5") (pintype "bidirectional"))
      (node (ref "J17") (pin "P6") (pinfunction "P6_P6") (pintype "bidirectional"))
      (node (ref "J2") (pin "2") (pinfunction "2_2") (pintype "passive"))
      (node (ref "J3") (pin "6") (pinfunction "VSS_6") (pintype "bidirectional"))
      (node (ref "J4") (pin "2") (pinfunction "2_2") (pintype "passive"))
      (node (ref "J5") (pin "2") (pinfunction "2_2") (pintype "passive"))
      (node (ref "J6") (pin "2") (pinfunction "2_2") (pintype "passive"))
      (node (ref "J7") (pin "2") (pinfunction "2_2") (pintype "passive"))
      (node (ref "J8") (pin "2") (pinfunction "2_2") (pintype "passive"))
      (node (ref "J9") (pin "2") (pinfunction "2_2") (pintype "passive"))
      (node (ref "R10") (pin "1") (pinfunction "1_1") (pintype "passive"))
      (node (ref "R12") (pin "1") (pinfunction "1_1") (pintype "passive"))
      (node (ref "R14") (pin "1") (pinfunction "1_1") (pintype "passive"))
      (node (ref "R16") (pin "1") (pinfunction "1_1") (pintype "passive"))
      (node (ref "R4") (pin "1") (pinfunction "1_1") (pintype "passive"))
      (node (ref "R46") (pin "1") (pinfunction "1_1") (pintype "passive"))
      (node (ref "R50") (pin "1") (pinfunction "1_1") (pintype "passive"))
      (node (ref "R6") (pin "1") (pinfunction "1_1") (pintype "passive"))
      (node (ref "R8") (pin "1") (pinfunction "1_1") (pintype "passive"))
      (node (ref "U1") (pin "10") (pinfunction "VSS_10") (pintype "passive"))
      (node (ref "U2") (pin "10") (pinfunction "VSS_10") (pintype "passive"))
      (node (ref "U3") (pin "7") (pinfunction "GND_7") (pintype "power_in"))
      (node (ref "U4") (pin "11") (pinfunction "EPAD_11") (pintype "passive"))
      (node (ref "U4") (pin "3") (pinfunction "PGND_3") (pintype "passive"))
      (node (ref "U4") (pin "9") (pinfunction "GND_9") (pintype "passive"))
      (node (ref "U5") (pin "2") (pinfunction "VSS_2") (pintype "passive"))
      (node (ref "U8") (pin "10") (pinfunction "GND_10") (pintype "power_in"))
      (node (ref "U8") (pin "12") (pinfunction "GND_12") (pintype "power_in"))
      (node (ref "U8") (pin "13") (pinfunction "GND_13") (pintype "power_in"))
      (node (ref "U8") (pin "16") (pinfunction "GND_16") (pintype "power_in"))
      (node (ref "U8") (pin "5") (pinfunction "GND_5") (pintype "power_in"))
    )
    (net (code "75") (name "Net-(D1-PadA)") (class "Default")
      (node (ref "D1") (pin "A") (pinfunction "A_A") (pintype "passive"))
      (node (ref "R17") (pin "1") (pinfunction "1_1") (pintype "passive"))
    )
    (net (code "76") (name "Net-(D2-PadA)") (class "Default")
      (node (ref "D2") (pin "A") (pinfunction "A_A") (pintype "passive"))
      (node (ref "R18") (pin "1") (pinfunction "1_1") (pintype "passive"))
    )
    (net (code "77") (name "Net-(D3-PadA)") (class "Default")
      (node (ref "D3") (pin "A") (pinfunction "A_A") (pintype "passive"))
      (node (ref "R19") (pin "1") (pinfunction "1_1") (pintype "passive"))
    )
    (net (code "78") (name "Net-(D4-PadA)") (class "Default")
      (node (ref "D4") (pin "A") (pinfunction "A_A") (pintype "passive"))
      (node (ref "R20") (pin "1") (pinfunction "1_1") (pintype "passive"))
    )
    (net (code "79") (name "Net-(D5-PadA)") (class "Default")
      (node (ref "D5") (pin "A") (pinfunction "A_A") (pintype "passive"))
      (node (ref "R21") (pin "1") (pinfunction "1_1") (pintype "passive"))
    )
    (net (code "80") (name "Net-(D6-PadA)") (class "Default")
      (node (ref "D6") (pin "A") (pinfunction "A_A") (pintype "passive"))
      (node (ref "R22") (pin "1") (pinfunction "1_1") (pintype "passive"))
    )
    (net (code "81") (name "Net-(D7-PadA)") (class "Default")
      (node (ref "D7") (pin "A") (pinfunction "A_A") (pintype "passive"))
      (node (ref "R23") (pin "1") (pinfunction "1_1") (pintype "passive"))
    )
    (net (code "82") (name "Net-(D8-PadA)") (class "Default")
      (node (ref "D8") (pin "A") (pinfunction "A_A") (pintype "passive"))
      (node (ref "R24") (pin "1") (pinfunction "1_1") (pintype "passive"))
    )
    (net (code "83") (name "Net-(D9-PadC)") (class "Default")
      (node (ref "D9") (pin "C") (pinfunction "C_C") (pintype "passive"))
      (node (ref "R45") (pin "1") (pinfunction "1_1") (pintype "passive"))
    )
    (net (code "84") (name "Net-(J3-DAT1)") (class "Default")
      (node (ref "J3") (pin "8") (pinfunction "DAT1_8") (pintype "bidirectional"))
      (node (ref "R26") (pin "2") (pinfunction "2_2") (pintype "passive"))
    )
    (net (code "85") (name "Net-(J3-DAT2)") (class "Default")
      (node (ref "J3") (pin "1") (pinfunction "DAT2_1") (pintype "bidirectional"))
      (node (ref "R25") (pin "2") (pinfunction "2_2") (pintype "passive"))
    )
    (net (code "86") (name "Net-(J17-Pad2)") (class "Default")
      (node (ref "J17") (pin "2") (pinfunction "2_2") (pintype "bidirectional"))
      (node (ref "R47") (pin "1") (pinfunction "1_1") (pintype "passive"))
    )
    (net (code "87") (name "Net-(J17-Pad3)") (class "Default")
      (node (ref "J17") (pin "3") (pinfunction "3_3") (pintype "bidirectional"))
      (node (ref "R48") (pin "1") (pinfunction "1_1") (pintype "passive"))
    )
    (net (code "88") (name "Net-(S1-1)") (class "Default")
      (node (ref "C1") (pin "1") (pinfunction "1_1") (pintype "passive"))
      (node (ref "S1") (pin "A2") (pinfunction "1_A2") (pintype "passive"))
    )
    (net (code "89") (name "Net-(S1-2)") (class "Default")
      (node (ref "R1") (pin "2") (pinfunction "2_2") (pintype "passive"))
      (node (ref "R2") (pin "2") (pinfunction "2_2") (pintype "passive"))
      (node (ref "S1") (pin "B2") (pinfunction "2_B2") (pintype "passive"))
    )
    (net (code "90") (name "Net-(U4-FB)") (class "Default")
      (node (ref "R49") (pin "1") (pinfunction "1_1") (pintype "passive"))
      (node (ref "R50") (pin "2") (pinfunction "2_2") (pintype "passive"))
      (node (ref "U4") (pin "10") (pinfunction "FB_10") (pintype "passive"))
    )
    (net (code "91") (name "Net-(U4-SW1)") (class "Default")
      (node (ref "U$1") (pin "2") (pinfunction "2_2") (pintype "passive"))
      (node (ref "U4") (pin "4") (pinfunction "SW1_4") (pintype "bidirectional"))
    )
    (net (code "92") (name "Net-(U4-SW2)") (class "Default")
      (node (ref "U$1") (pin "1") (pinfunction "1_1") (pintype "passive"))
      (node (ref "U4") (pin "2") (pinfunction "SW2_2") (pintype "bidirectional"))
    )
    (net (code "93") (name "Net-(U5-PROG)") (class "Default")
      (node (ref "R46") (pin "2") (pinfunction "2_2") (pintype "passive"))
      (node (ref "U5") (pin "5") (pinfunction "PROG_5") (pintype "passive"))
    )
    (net (code "94") (name "Net-(U5-STAT)") (class "Default")
      (node (ref "R45") (pin "2") (pinfunction "2_2") (pintype "passive"))
      (node (ref "U5") (pin "1") (pinfunction "STAT_1") (pintype "passive"))
    )
    (net (code "95") (name "unconnected-(IC1-AN9{slash}RPI27{slash}RA11-Pad12)") (class "Default")
      (node (ref "IC1") (pin "12") (pinfunction "AN9/RPI27/RA11_12") (pintype "bidirectional"))
    )
    (net (code "96") (name "unconnected-(IC1-AN12{slash}C2IN2-{slash}C5IN2-{slash}~{U2RTS}{slash}BCLK2{slash}FLT5{slash}PMA11{slash}RE12-Pad27)") (class "Default")
      (node (ref "IC1") (pin "27") (pinfunction "AN12/C2IN2-/C5IN2-/~{U2RTS}/BCLK2/FLT5/PMA11/RE12_27") (pintype "bidirectional"))
    )
    (net (code "97") (name "unconnected-(IC1-AN13{slash}C3IN2-{slash}~{U2CTS}{slash}FLT6{slash}PMA10{slash}RE13-Pad28)") (class "Default")
      (node (ref "IC1") (pin "28") (pinfunction "AN13/C3IN2-/~{U2CTS}/FLT6/PMA10/RE13_28") (pintype "bidirectional"))
    )
    (net (code "98") (name "unconnected-(IC1-AN14{slash}RPI94{slash}FLT7{slash}PMA1{slash}RE14-Pad29)") (class "Default")
      (node (ref "IC1") (pin "29") (pinfunction "AN14/RPI94/FLT7/PMA1/RE14_29") (pintype "bidirectional"))
    )
    (net (code "99") (name "unconnected-(IC1-AN15{slash}RPI95{slash}FLT8{slash}PMA0{slash}RE15-Pad30)") (class "Default")
      (node (ref "IC1") (pin "30") (pinfunction "AN15/RPI95/FLT8/PMA0/RE15_30") (pintype "bidirectional"))
    )
    (net (code "100") (name "unconnected-(IC1-AN16{slash}RPI121{slash}PMA2{slash}RG9-Pad8)") (class "Default")
      (node (ref "IC1") (pin "8") (pinfunction "AN16/RPI121/PMA2/RG9_8") (pintype "bidirectional"))
    )
    (net (code "101") (name "unconnected-(IC1-AN17{slash}ASDA1{slash}RP120{slash}PMA3{slash}RG8-Pad6)") (class "Default")
      (node (ref "IC1") (pin "6") (pinfunction "AN17/ASDA1/RP120/PMA3/RG8_6") (pintype "bidirectional"))
    )
    (net (code "102") (name "unconnected-(IC1-AN18{slash}ASCL1{slash}RPI119{slash}PMA4{slash}RG7-Pad5)") (class "Default")
      (node (ref "IC1") (pin "5") (pinfunction "AN18/ASCL1/RPI119/PMA4/RG7_5") (pintype "bidirectional"))
    )
    (net (code "103") (name "unconnected-(IC1-AN19{slash}RP118{slash}PMA5{slash}RG6-Pad4)") (class "Default")
      (node (ref "IC1") (pin "4") (pinfunction "AN19/RP118/PMA5/RG6_4") (pintype "bidirectional"))
    )
    (net (code "104") (name "unconnected-(IC1-AN48{slash}CVREF2O{slash}RPI58{slash}PMCS1{slash}RC10-Pad45)") (class "Default")
      (node (ref "IC1") (pin "45") (pinfunction "AN48/CVREF2O/RPI58/PMCS1/RC10_45") (pintype "bidirectional"))
    )
    (net (code "105") (name "unconnected-(IC1-AN49{slash}OSC1{slash}CLKI{slash}RPI60{slash}RC12-Pad39)") (class "Default")
      (node (ref "IC1") (pin "39") (pinfunction "AN49/OSC1/CLKI/RPI60/RC12_39") (pintype "bidirectional"))
    )
    (net (code "106") (name "unconnected-(IC1-FLT32{slash}SCL2{slash}RP36{slash}PMA8{slash}RB4-Pad32)") (class "Default")
      (node (ref "IC1") (pin "32") (pinfunction "FLT32/SCL2/RP36/PMA8/RB4_32") (pintype "bidirectional"))
    )
    (net (code "107") (name "unconnected-(IC1-OA2IN+{slash}AN1{slash}C2IN1+{slash}RPI17{slash}RA1-Pad14)") (class "Default")
      (node (ref "IC1") (pin "14") (pinfunction "OA2IN+/AN1/C2IN1+/RPI17/RA1_14") (pintype "bidirectional"))
    )
    (net (code "108") (name "unconnected-(IC1-OA2OUT{slash}AN0{slash}C2IN4-{slash}C4IN3-{slash}RPI16{slash}RA0-Pad13)") (class "Default")
      (node (ref "IC1") (pin "13") (pinfunction "OA2OUT/AN0/C2IN4-/C4IN3-/RPI16/RA0_13") (pintype "bidirectional"))
    )
    (net (code "109") (name "unconnected-(IC1-OA5OUT{slash}AN25{slash}C5IN4-{slash}RP39{slash}INT0{slash}RB7-Pad46)") (class "Default")
      (node (ref "IC1") (pin "46") (pinfunction "OA5OUT/AN25/C5IN4-/RP39/INT0/RB7_46") (pintype "bidirectional"))
    )
    (net (code "110") (name "unconnected-(IC1-OSC2{slash}CLKO{slash}RPI63{slash}RC15-Pad40)") (class "Default")
      (node (ref "IC1") (pin "40") (pinfunction "OSC2/CLKO/RPI63/RC15_40") (pintype "bidirectional"))
    )
    (net (code "111") (name "unconnected-(IC1-PGEC2{slash}ASCL2{slash}RP38{slash}PMCS2{slash}RB6-Pad44)") (class "Default")
      (node (ref "IC1") (pin "44") (pinfunction "PGEC2/ASCL2/RP38/PMCS2/RB6_44") (pintype "bidirectional"))
    )
    (net (code "112") (name "unconnected-(IC1-PGEC3{slash}VREF+{slash}CVREF+{slash}OA1OUT{slash}AN3{slash}C1IN4-{slash}C4IN2-{slash}RPI33{slash}CTED1{slash}RB1-Pad16)") (class "Default")
      (node (ref "IC1") (pin "16") (pinfunction "PGEC3/VREF+/CVREF+/OA1OUT/AN3/C1IN4-/C4IN2-/RPI33/CTED1/RB1_16") (pintype "bidirectional"))
    )
    (net (code "113") (name "unconnected-(IC1-PGED2{slash}ASDA2{slash}RP37{slash}RB5-Pad43)") (class "Default")
      (node (ref "IC1") (pin "43") (pinfunction "PGED2/ASDA2/RP37/RB5_43") (pintype "bidirectional"))
    )
    (net (code "114") (name "unconnected-(IC1-RPI46{slash}PWM1H{slash}T3CK{slash}T7CK{slash}PMD6{slash}RB14-Pad2)") (class "Default")
      (node (ref "IC1") (pin "2") (pinfunction "RPI46/PWM1H/T3CK/T7CK/PMD6/RB14_2") (pintype "bidirectional"))
    )
    (net (code "115") (name "unconnected-(IC1-RPI47{slash}PWM1L{slash}T5CK{slash}T6CK{slash}PMD7{slash}RB15-Pad3)") (class "Default")
      (node (ref "IC1") (pin "3") (pinfunction "RPI47/PWM1L/T5CK/T6CK/PMD7/RB15_3") (pintype "bidirectional"))
    )
    (net (code "116") (name "unconnected-(IC1-RPI72{slash}RD8-Pad42)") (class "Default")
      (node (ref "IC1") (pin "42") (pinfunction "RPI72/RD8_42") (pintype "bidirectional"))
    )
    (net (code "117") (name "unconnected-(IC1-RPI96{slash}RF0-Pad58)") (class "Default")
      (node (ref "IC1") (pin "58") (pinfunction "RPI96/RF0_58") (pintype "bidirectional"))
    )
    (net (code "118") (name "unconnected-(IC1-SDA2{slash}RPI24{slash}PMA9{slash}RA8-Pad31)") (class "Default")
      (node (ref "IC1") (pin "31") (pinfunction "SDA2/RPI24/PMA9/RA8_31") (pintype "bidirectional"))
    )
    (net (code "119") (name "unconnected-(IC1-SOSCI{slash}RPI61{slash}RC13-Pad47)") (class "Default")
      (node (ref "IC1") (pin "47") (pinfunction "SOSCI/RPI61/RC13_47") (pintype "bidirectional"))
    )
    (net (code "120") (name "unconnected-(IC1-TDI{slash}PWM4L{slash}PMD5{slash}RA7-Pad1)") (class "Default")
      (node (ref "IC1") (pin "1") (pinfunction "TDI/PWM4L/PMD5/RA7_1") (pintype "bidirectional"))
    )
    (net (code "121") (name "unconnected-(J3-A-PadCD_A)") (class "Default")
      (node (ref "J3") (pin "CD_A") (pinfunction "A_CD_A") (pintype "bidirectional"))
    )
    (net (code "122") (name "unconnected-(J3-B-PadCD_B)") (class "Default")
      (node (ref "J3") (pin "CD_B") (pinfunction "B_CD_B") (pintype "bidirectional"))
    )
    (net (code "123") (name "unconnected-(J17-Pad4)") (class "Default")
      (node (ref "J17") (pin "4") (pinfunction "4_4") (pintype "bidirectional"))
    )
    (net (code "124") (name "unconnected-(U1-~{INT}-Pad17)") (class "Default")
      (node (ref "U1") (pin "17") (pinfunction "~{INT}_17") (pintype "passive"))
    )
    (net (code "125") (name "unconnected-(U2-~{INT}-Pad17)") (class "Default")
      (node (ref "U2") (pin "17") (pinfunction "~{INT}_17") (pintype "passive"))
    )
    (net (code "126") (name "unconnected-(U3-NC-Pad9)") (class "Default")
      (node (ref "U3") (pin "9") (pinfunction "NC_9") (pintype "passive"))
    )
    (net (code "127") (name "unconnected-(U3-NC_2-Pad6)") (class "Default")
      (node (ref "U3") (pin "6") (pinfunction "NC_2_6") (pintype "passive"))
    )
    (net (code "128") (name "unconnected-(U3-OE-Pad8)") (class "Default")
      (node (ref "U3") (pin "8") (pinfunction "OE_8") (pintype "output"))
    )
    (net (code "129") (name "unconnected-(U4-EN-Pad6)") (class "Default")
      (node (ref "U4") (pin "6") (pinfunction "EN_6") (pintype "passive"))
    )
    (net (code "130") (name "unconnected-(U4-MODE{slash}SYNC-Pad7)") (class "Default")
      (node (ref "U4") (pin "7") (pinfunction "MODE/SYNC_7") (pintype "passive"))
    )
    (net (code "131") (name "unconnected-(U8-CS-Pad8)") (class "Default")
      (node (ref "U8") (pin "8") (pinfunction "CS_8") (pintype "input"))
    )
  )
)
